# star-tracker-camera-board.net
KiCad netlist of a schematic drawn in EAGLE
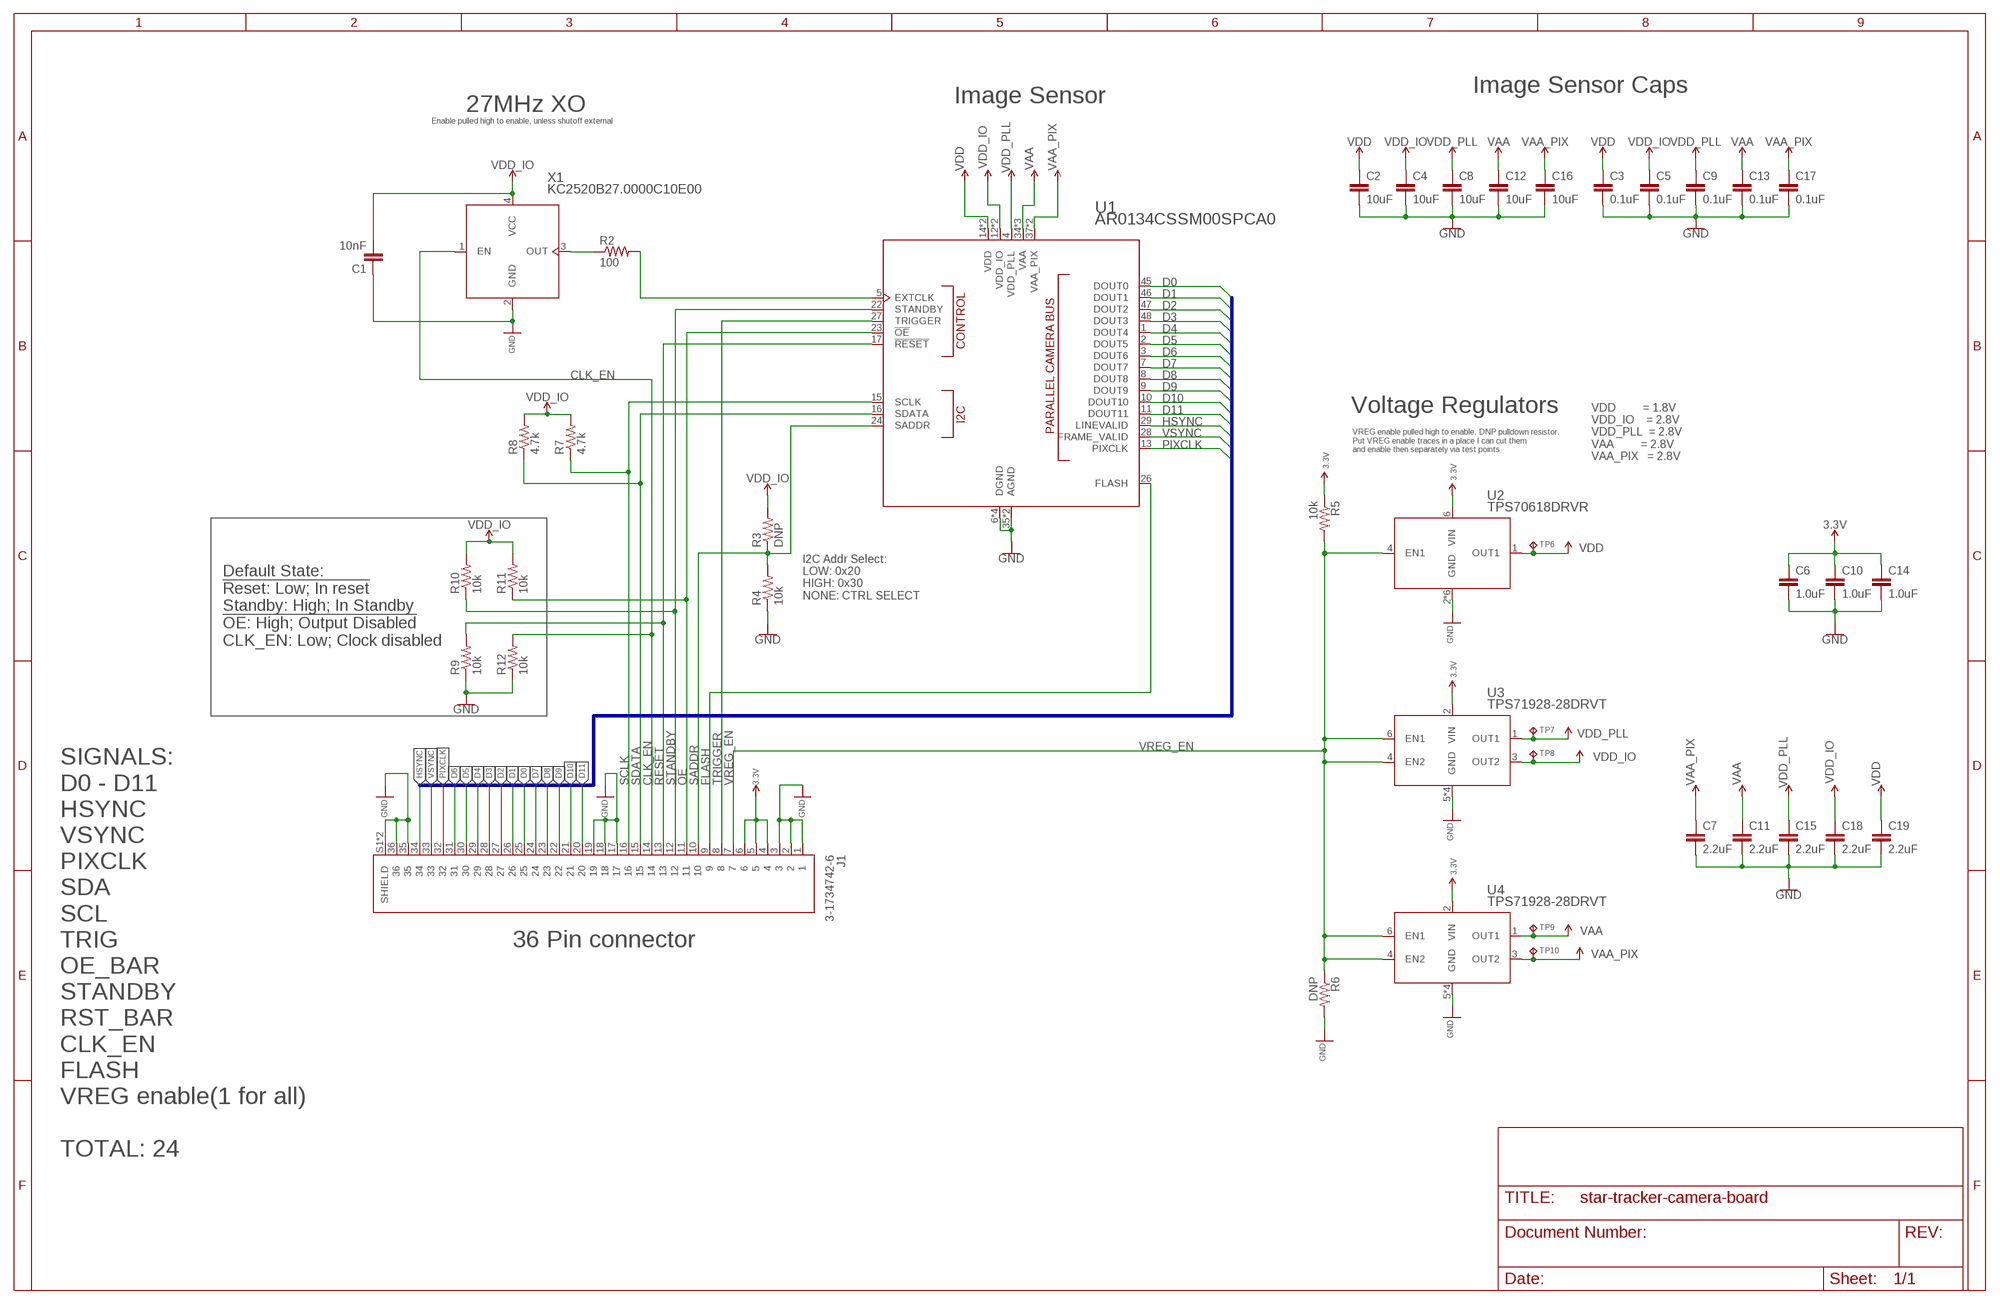
[diagram p0: schematic, sheet 1]

(export (version "E")
  (design (tool "Eeschema 10.0.6"))
  (components
    (comp (ref "C1")
      (value "10nF")
      (footprint "eagle-import:.0402-A-NOSILK")
      (libsource (lib "eagle-import") (part "C-EU0402-A-NOSILK"))
    )
    (comp (ref "C2")
      (value "10uF")
      (footprint "eagle-import:.0603-C-NOSILK")
      (libsource (lib "eagle-import") (part "C-EU0603-C-NOSILK"))
    )
    (comp (ref "C3")
      (value "0.1uF")
      (footprint "eagle-import:.0402-B-NOSILK")
      (libsource (lib "eagle-import") (part "C-EU0402-B-NOSILK"))
    )
    (comp (ref "C4")
      (value "10uF")
      (footprint "eagle-import:.0603-C-NOSILK")
      (libsource (lib "eagle-import") (part "C-EU0603-C-NOSILK"))
    )
    (comp (ref "C5")
      (value "0.1uF")
      (footprint "eagle-import:.0402-B-NOSILK")
      (libsource (lib "eagle-import") (part "C-EU0402-B-NOSILK"))
    )
    (comp (ref "C6")
      (value "1.0uF")
      (footprint "eagle-import:.0603-C-NOSILK")
      (libsource (lib "eagle-import") (part "C-EU0603-C-NOSILK"))
    )
    (comp (ref "C7")
      (value "2.2uF")
      (footprint "eagle-import:.0603-C-NOSILK")
      (libsource (lib "eagle-import") (part "C-EU0603-C-NOSILK"))
    )
    (comp (ref "C8")
      (value "10uF")
      (footprint "eagle-import:.0603-C-NOSILK")
      (libsource (lib "eagle-import") (part "C-EU0603-C-NOSILK"))
    )
    (comp (ref "C9")
      (value "0.1uF")
      (footprint "eagle-import:.0402-B-NOSILK")
      (libsource (lib "eagle-import") (part "C-EU0402-B-NOSILK"))
    )
    (comp (ref "C10")
      (value "1.0uF")
      (footprint "eagle-import:.0603-C-NOSILK")
      (libsource (lib "eagle-import") (part "C-EU0603-C-NOSILK"))
    )
    (comp (ref "C11")
      (value "2.2uF")
      (footprint "eagle-import:.0603-C-NOSILK")
      (libsource (lib "eagle-import") (part "C-EU0603-C-NOSILK"))
    )
    (comp (ref "C12")
      (value "10uF")
      (footprint "eagle-import:.0603-C-NOSILK")
      (libsource (lib "eagle-import") (part "C-EU0603-C-NOSILK"))
    )
    (comp (ref "C13")
      (value "0.1uF")
      (footprint "eagle-import:.0402-B-NOSILK")
      (libsource (lib "eagle-import") (part "C-EU0402-B-NOSILK"))
    )
    (comp (ref "C14")
      (value "1.0uF")
      (footprint "eagle-import:.0603-C-NOSILK")
      (libsource (lib "eagle-import") (part "C-EU0603-C-NOSILK"))
    )
    (comp (ref "C15")
      (value "2.2uF")
      (footprint "eagle-import:.0603-C-NOSILK")
      (libsource (lib "eagle-import") (part "C-EU0603-C-NOSILK"))
    )
    (comp (ref "C16")
      (value "10uF")
      (footprint "eagle-import:.0603-C-NOSILK")
      (libsource (lib "eagle-import") (part "C-EU0603-C-NOSILK"))
    )
    (comp (ref "C17")
      (value "0.1uF")
      (footprint "eagle-import:.0402-B-NOSILK")
      (libsource (lib "eagle-import") (part "C-EU0402-B-NOSILK"))
    )
    (comp (ref "C18")
      (value "2.2uF")
      (footprint "eagle-import:.0603-C-NOSILK")
      (libsource (lib "eagle-import") (part "C-EU0603-C-NOSILK"))
    )
    (comp (ref "C19")
      (value "2.2uF")
      (footprint "eagle-import:.0603-C-NOSILK")
      (libsource (lib "eagle-import") (part "C-EU0603-C-NOSILK"))
    )
    (comp (ref "J1")
      (value "3-1734742-6")
      (footprint "eagle-import:TE_3-1734742-6")
      (libsource (lib "eagle-import") (part "3-1734742-6"))
    )
    (comp (ref "R2")
      (value "100")
      (footprint "eagle-import:.0402-B")
      (libsource (lib "eagle-import") (part "R-US_0402-B"))
    )
    (comp (ref "R3")
      (value "DNP")
      (footprint "eagle-import:.0402-B-NOSILK")
      (libsource (lib "eagle-import") (part "R-US_0402-B-NOSILK"))
    )
    (comp (ref "R4")
      (value "10k")
      (footprint "eagle-import:.0402-B-NOSILK")
      (libsource (lib "eagle-import") (part "R-US_0402-B-NOSILK"))
    )
    (comp (ref "R5")
      (value "10k")
      (footprint "eagle-import:.0402-B-NOSILK")
      (libsource (lib "eagle-import") (part "R-US_0402-B-NOSILK"))
    )
    (comp (ref "R6")
      (value "DNP")
      (footprint "eagle-import:.0402-B-NOSILK")
      (libsource (lib "eagle-import") (part "R-US_0402-B-NOSILK"))
    )
    (comp (ref "R7")
      (value "4.7k")
      (footprint "eagle-import:.0402-B-NOSILK")
      (libsource (lib "eagle-import") (part "R-US_0402-B-NOSILK"))
    )
    (comp (ref "R8")
      (value "4.7k")
      (footprint "eagle-import:.0402-B-NOSILK")
      (libsource (lib "eagle-import") (part "R-US_0402-B-NOSILK"))
    )
    (comp (ref "R9")
      (value "10k")
      (footprint "eagle-import:.0402-B")
      (libsource (lib "eagle-import") (part "R-US_0402-B"))
    )
    (comp (ref "R10")
      (value "10k")
      (footprint "eagle-import:.0402-B")
      (libsource (lib "eagle-import") (part "R-US_0402-B"))
    )
    (comp (ref "R11")
      (value "10k")
      (footprint "eagle-import:.0402-B")
      (libsource (lib "eagle-import") (part "R-US_0402-B"))
    )
    (comp (ref "R12")
      (value "10k")
      (footprint "eagle-import:.0402-B")
      (libsource (lib "eagle-import") (part "R-US_0402-B"))
    )
    (comp (ref "TP6")
      (value "TPTP06R")
      (footprint "eagle-import:TP06R")
      (libsource (lib "eagle-import") (part "TPTP06R"))
    )
    (comp (ref "TP7")
      (value "TPTP06R")
      (footprint "eagle-import:TP06R")
      (libsource (lib "eagle-import") (part "TPTP06R"))
    )
    (comp (ref "TP8")
      (value "TPTP06R")
      (footprint "eagle-import:TP06R")
      (libsource (lib "eagle-import") (part "TPTP06R"))
    )
    (comp (ref "TP9")
      (value "TPTP06R")
      (footprint "eagle-import:TP06R")
      (libsource (lib "eagle-import") (part "TPTP06R"))
    )
    (comp (ref "TP10")
      (value "TPTP06R")
      (footprint "eagle-import:TP06R")
      (libsource (lib "eagle-import") (part "TPTP06R"))
    )
    (comp (ref "U1")
      (value "AR0134CSSM00SPCA0")
      (footprint "eagle-import:AR0134CSSM00SPCA0")
      (libsource (lib "eagle-import") (part "AR0134CSSM00SPCA0"))
    )
    (comp (ref "U2")
      (value "TPS70618DRVR")
      (footprint "eagle-import:DRV6_1P6X1")
      (libsource (lib "eagle-import") (part "TPS70618DRVR"))
    )
    (comp (ref "U3")
      (value "TPS71928-28DRVT")
      (footprint "eagle-import:DRV6_1P6X1")
      (fields (field (name "MPN") "TPS71928-28DRVR"))
      (libsource (lib "eagle-import") (part "TPS71928-28DRVT"))
    )
    (comp (ref "U4")
      (value "TPS71928-28DRVT")
      (footprint "eagle-import:DRV6_1P6X1")
      (fields (field (name "MPN") "TPS71928-28DRVR"))
      (libsource (lib "eagle-import") (part "TPS71928-28DRVT"))
    )
    (comp (ref "X1")
      (value "KC2520B27.0000C10E00")
      (footprint "eagle-import:OSC_KYOCERA_KC2520B")
      (libsource (lib "eagle-import") (part "KC2520B27.0000C10E00"))
    )
  )
  (nets
    (net (code "1") (name "/CLK_EN") (class "Default")
      (node (ref "J1") (pin "14") (pinfunction "14_14") (pintype "passive"))
      (node (ref "R12") (pin "2") (pinfunction "2_2") (pintype "passive"))
      (node (ref "X1") (pin "1") (pinfunction "EN_1") (pintype "passive"))
    )
    (net (code "2") (name "/FLASH") (class "Default")
      (node (ref "J1") (pin "9") (pinfunction "9_9") (pintype "passive"))
      (node (ref "U1") (pin "26") (pinfunction "FLASH_26") (pintype "bidirectional"))
    )
    (net (code "3") (name "/SADDR") (class "Default")
      (node (ref "J1") (pin "10") (pinfunction "10_10") (pintype "passive"))
      (node (ref "R3") (pin "1") (pinfunction "1_1") (pintype "passive"))
      (node (ref "R4") (pin "2") (pinfunction "2_2") (pintype "passive"))
      (node (ref "U1") (pin "24") (pinfunction "SADDR_24") (pintype "bidirectional"))
    )
    (net (code "4") (name "/SCLK") (class "Default")
      (node (ref "J1") (pin "16") (pinfunction "16_16") (pintype "passive"))
      (node (ref "R7") (pin "1") (pinfunction "1_1") (pintype "passive"))
      (node (ref "U1") (pin "15") (pinfunction "SCLK_15") (pintype "bidirectional"))
    )
    (net (code "5") (name "/SDATA") (class "Default")
      (node (ref "J1") (pin "15") (pinfunction "15_15") (pintype "passive"))
      (node (ref "R8") (pin "1") (pinfunction "1_1") (pintype "passive"))
      (node (ref "U1") (pin "16") (pinfunction "SDATA_16") (pintype "bidirectional"))
    )
    (net (code "6") (name "/STANDBY") (class "Default")
      (node (ref "J1") (pin "12") (pinfunction "12_12") (pintype "passive"))
      (node (ref "R10") (pin "1") (pinfunction "1_1") (pintype "passive"))
      (node (ref "U1") (pin "22") (pinfunction "STANDBY_22") (pintype "bidirectional"))
    )
    (net (code "7") (name "/TRIGGER") (class "Default")
      (node (ref "J1") (pin "8") (pinfunction "8_8") (pintype "passive"))
      (node (ref "U1") (pin "27") (pinfunction "TRIGGER_27") (pintype "bidirectional"))
    )
    (net (code "8") (name "/VREG_EN") (class "Default")
      (node (ref "J1") (pin "7") (pinfunction "7_7") (pintype "passive"))
      (node (ref "R5") (pin "2") (pinfunction "2_2") (pintype "passive"))
      (node (ref "R6") (pin "1") (pinfunction "1_1") (pintype "passive"))
      (node (ref "U2") (pin "4") (pinfunction "EN1_4") (pintype "passive"))
      (node (ref "U3") (pin "4") (pinfunction "EN2_4") (pintype "passive"))
      (node (ref "U3") (pin "6") (pinfunction "EN1_6") (pintype "passive"))
      (node (ref "U4") (pin "4") (pinfunction "EN2_4") (pintype "passive"))
      (node (ref "U4") (pin "6") (pinfunction "EN1_6") (pintype "passive"))
    )
    (net (code "9") (name "/~{OE}") (class "Default")
      (node (ref "J1") (pin "11") (pinfunction "11_11") (pintype "passive"))
      (node (ref "R11") (pin "1") (pinfunction "1_1") (pintype "passive"))
      (node (ref "U1") (pin "23") (pinfunction "~{OE}_23") (pintype "bidirectional"))
    )
    (net (code "10") (name "/~{RESET}") (class "Default")
      (node (ref "J1") (pin "13") (pinfunction "13_13") (pintype "passive"))
      (node (ref "R9") (pin "2") (pinfunction "2_2") (pintype "passive"))
      (node (ref "U1") (pin "17") (pinfunction "~{RESET}_17") (pintype "bidirectional"))
    )
    (net (code "11") (name "3.3V") (class "Default")
      (node (ref "C10") (pin "1") (pinfunction "1_1") (pintype "passive"))
      (node (ref "C14") (pin "1") (pinfunction "1_1") (pintype "passive"))
      (node (ref "C6") (pin "1") (pinfunction "1_1") (pintype "passive"))
      (node (ref "J1") (pin "4") (pinfunction "4_4") (pintype "passive"))
      (node (ref "J1") (pin "5") (pinfunction "5_5") (pintype "passive"))
      (node (ref "J1") (pin "6") (pinfunction "6_6") (pintype "passive"))
      (node (ref "R5") (pin "1") (pinfunction "1_1") (pintype "passive"))
      (node (ref "U2") (pin "6") (pinfunction "VIN_6") (pintype "input"))
      (node (ref "U3") (pin "2") (pinfunction "VIN_2") (pintype "power_in"))
      (node (ref "U4") (pin "2") (pinfunction "VIN_2") (pintype "power_in"))
    )
    (net (code "12") (name "D0") (class "Default")
      (node (ref "J1") (pin "25") (pinfunction "25_25") (pintype "passive"))
      (node (ref "U1") (pin "45") (pinfunction "DOUT0_45") (pintype "bidirectional"))
    )
    (net (code "13") (name "D1") (class "Default")
      (node (ref "J1") (pin "26") (pinfunction "26_26") (pintype "passive"))
      (node (ref "U1") (pin "46") (pinfunction "DOUT1_46") (pintype "bidirectional"))
    )
    (net (code "14") (name "D2") (class "Default")
      (node (ref "J1") (pin "27") (pinfunction "27_27") (pintype "passive"))
      (node (ref "U1") (pin "47") (pinfunction "DOUT2_47") (pintype "bidirectional"))
    )
    (net (code "15") (name "D3") (class "Default")
      (node (ref "J1") (pin "28") (pinfunction "28_28") (pintype "passive"))
      (node (ref "U1") (pin "48") (pinfunction "DOUT3_48") (pintype "bidirectional"))
    )
    (net (code "16") (name "D4") (class "Default")
      (node (ref "J1") (pin "29") (pinfunction "29_29") (pintype "passive"))
      (node (ref "U1") (pin "1") (pinfunction "DOUT4_1") (pintype "bidirectional"))
    )
    (net (code "17") (name "D5") (class "Default")
      (node (ref "J1") (pin "30") (pinfunction "30_30") (pintype "passive"))
      (node (ref "U1") (pin "2") (pinfunction "DOUT5_2") (pintype "bidirectional"))
    )
    (net (code "18") (name "D6") (class "Default")
      (node (ref "J1") (pin "31") (pinfunction "31_31") (pintype "passive"))
      (node (ref "U1") (pin "3") (pinfunction "DOUT6_3") (pintype "bidirectional"))
    )
    (net (code "19") (name "D7") (class "Default")
      (node (ref "J1") (pin "24") (pinfunction "24_24") (pintype "passive"))
      (node (ref "U1") (pin "7") (pinfunction "DOUT7_7") (pintype "bidirectional"))
    )
    (net (code "20") (name "D8") (class "Default")
      (node (ref "J1") (pin "23") (pinfunction "23_23") (pintype "passive"))
      (node (ref "U1") (pin "8") (pinfunction "DOUT8_8") (pintype "bidirectional"))
    )
    (net (code "21") (name "D9") (class "Default")
      (node (ref "J1") (pin "22") (pinfunction "22_22") (pintype "passive"))
      (node (ref "U1") (pin "9") (pinfunction "DOUT9_9") (pintype "bidirectional"))
    )
    (net (code "22") (name "D10") (class "Default")
      (node (ref "J1") (pin "21") (pinfunction "21_21") (pintype "passive"))
      (node (ref "U1") (pin "10") (pinfunction "DOUT10_10") (pintype "bidirectional"))
    )
    (net (code "23") (name "D11") (class "Default")
      (node (ref "J1") (pin "20") (pinfunction "20_20") (pintype "passive"))
      (node (ref "U1") (pin "11") (pinfunction "DOUT11_11") (pintype "bidirectional"))
    )
    (net (code "24") (name "GND") (class "Default")
      (node (ref "C1") (pin "1") (pinfunction "1_1") (pintype "passive"))
      (node (ref "C10") (pin "2") (pinfunction "2_2") (pintype "passive"))
      (node (ref "C11") (pin "2") (pinfunction "2_2") (pintype "passive"))
      (node (ref "C12") (pin "2") (pinfunction "2_2") (pintype "passive"))
      (node (ref "C13") (pin "2") (pinfunction "2_2") (pintype "passive"))
      (node (ref "C14") (pin "2") (pinfunction "2_2") (pintype "passive"))
      (node (ref "C15") (pin "2") (pinfunction "2_2") (pintype "passive"))
      (node (ref "C16") (pin "2") (pinfunction "2_2") (pintype "passive"))
      (node (ref "C17") (pin "2") (pinfunction "2_2") (pintype "passive"))
      (node (ref "C18") (pin "2") (pinfunction "2_2") (pintype "passive"))
      (node (ref "C19") (pin "2") (pinfunction "2_2") (pintype "passive"))
      (node (ref "C2") (pin "2") (pinfunction "2_2") (pintype "passive"))
      (node (ref "C3") (pin "2") (pinfunction "2_2") (pintype "passive"))
      (node (ref "C4") (pin "2") (pinfunction "2_2") (pintype "passive"))
      (node (ref "C5") (pin "2") (pinfunction "2_2") (pintype "passive"))
      (node (ref "C6") (pin "2") (pinfunction "2_2") (pintype "passive"))
      (node (ref "C7") (pin "2") (pinfunction "2_2") (pintype "passive"))
      (node (ref "C8") (pin "2") (pinfunction "2_2") (pintype "passive"))
      (node (ref "C9") (pin "2") (pinfunction "2_2") (pintype "passive"))
      (node (ref "J1") (pin "1") (pinfunction "1_1") (pintype "passive"))
      (node (ref "J1") (pin "17") (pinfunction "17_17") (pintype "passive"))
      (node (ref "J1") (pin "18") (pinfunction "18_18") (pintype "passive"))
      (node (ref "J1") (pin "19") (pinfunction "19_19") (pintype "passive"))
      (node (ref "J1") (pin "2") (pinfunction "2_2") (pintype "passive"))
      (node (ref "J1") (pin "3") (pinfunction "3_3") (pintype "passive"))
      (node (ref "J1") (pin "35") (pinfunction "35_35") (pintype "passive"))
      (node (ref "J1") (pin "36") (pinfunction "36_36") (pintype "passive"))
      (node (ref "J1") (pin "S1") (pinfunction "SHIELD_S1") (pintype "passive"))
      (node (ref "J1") (pin "S2") (pinfunction "SHIELD_S2") (pintype "passive"))
      (node (ref "R12") (pin "1") (pinfunction "1_1") (pintype "passive"))
      (node (ref "R4") (pin "1") (pinfunction "1_1") (pintype "passive"))
      (node (ref "R6") (pin "2") (pinfunction "2_2") (pintype "passive"))
      (node (ref "R9") (pin "1") (pinfunction "1_1") (pintype "passive"))
      (node (ref "U1") (pin "25") (pinfunction "DGND_25") (pintype "power_in"))
      (node (ref "U1") (pin "30") (pinfunction "DGND_30") (pintype "power_in"))
      (node (ref "U1") (pin "35") (pinfunction "AGND_35") (pintype "power_in"))
      (node (ref "U1") (pin "39") (pinfunction "AGND_39") (pintype "power_in"))
      (node (ref "U1") (pin "44") (pinfunction "DGND_44") (pintype "power_in"))
      (node (ref "U1") (pin "6") (pinfunction "DGND_6") (pintype "power_in"))
      (node (ref "U2") (pin "2") (pinfunction "GND_2") (pintype "power_in"))
      (node (ref "U2") (pin "3") (pinfunction "GND_3") (pintype "power_in"))
      (node (ref "U2") (pin "5") (pinfunction "GND_5") (pintype "power_in"))
      (node (ref "U2") (pin "7") (pinfunction "GND_7") (pintype "power_in"))
      (node (ref "U2") (pin "8") (pinfunction "GND_8") (pintype "power_in"))
      (node (ref "U2") (pin "9") (pinfunction "GND_9") (pintype "power_in"))
      (node (ref "U3") (pin "5") (pinfunction "GND_5") (pintype "power_in"))
      (node (ref "U3") (pin "7") (pinfunction "GND_7") (pintype "power_in"))
      (node (ref "U3") (pin "8") (pinfunction "GND_8") (pintype "power_in"))
      (node (ref "U3") (pin "9") (pinfunction "GND_9") (pintype "power_in"))
      (node (ref "U4") (pin "5") (pinfunction "GND_5") (pintype "power_in"))
      (node (ref "U4") (pin "7") (pinfunction "GND_7") (pintype "power_in"))
      (node (ref "U4") (pin "8") (pinfunction "GND_8") (pintype "power_in"))
      (node (ref "U4") (pin "9") (pinfunction "GND_9") (pintype "power_in"))
      (node (ref "X1") (pin "2") (pinfunction "GND_2") (pintype "power_in"))
    )
    (net (code "25") (name "HSYNC") (class "Default")
      (node (ref "J1") (pin "34") (pinfunction "34_34") (pintype "passive"))
      (node (ref "U1") (pin "29") (pinfunction "LINEVALID_29") (pintype "bidirectional"))
    )
    (net (code "26") (name "Net-(U1-EXTCLK)") (class "Default")
      (node (ref "R2") (pin "2") (pinfunction "2_2") (pintype "passive"))
      (node (ref "U1") (pin "5") (pinfunction "EXTCLK_5") (pintype "bidirectional"))
    )
    (net (code "27") (name "Net-(X1-OUT)") (class "Default")
      (node (ref "R2") (pin "1") (pinfunction "1_1") (pintype "passive"))
      (node (ref "X1") (pin "3") (pinfunction "OUT_3") (pintype "output"))
    )
    (net (code "28") (name "PIXCLK") (class "Default")
      (node (ref "J1") (pin "32") (pinfunction "32_32") (pintype "passive"))
      (node (ref "U1") (pin "13") (pinfunction "PIXCLK_13") (pintype "bidirectional"))
    )
    (net (code "29") (name "VAA") (class "Default")
      (node (ref "C11") (pin "1") (pinfunction "1_1") (pintype "passive"))
      (node (ref "C12") (pin "1") (pinfunction "1_1") (pintype "passive"))
      (node (ref "C13") (pin "1") (pinfunction "1_1") (pintype "passive"))
      (node (ref "TP9") (pin "TP") (pinfunction "TP_TP") (pintype "input"))
      (node (ref "U1") (pin "34") (pinfunction "VAA_34") (pintype "power_in"))
      (node (ref "U1") (pin "36") (pinfunction "VAA_36") (pintype "power_in"))
      (node (ref "U1") (pin "40") (pinfunction "VAA_40") (pintype "power_in"))
      (node (ref "U4") (pin "1") (pinfunction "OUT1_1") (pintype "power_in"))
    )
    (net (code "30") (name "VAA_PIX") (class "Default")
      (node (ref "C16") (pin "1") (pinfunction "1_1") (pintype "passive"))
      (node (ref "C17") (pin "1") (pinfunction "1_1") (pintype "passive"))
      (node (ref "C7") (pin "1") (pinfunction "1_1") (pintype "passive"))
      (node (ref "TP10") (pin "TP") (pinfunction "TP_TP") (pintype "input"))
      (node (ref "U1") (pin "37") (pinfunction "VAA_PIX_37") (pintype "power_in"))
      (node (ref "U1") (pin "38") (pinfunction "VAA_PIX_38") (pintype "power_in"))
      (node (ref "U4") (pin "3") (pinfunction "OUT2_3") (pintype "power_in"))
    )
    (net (code "31") (name "VDD") (class "Default")
      (node (ref "C19") (pin "1") (pinfunction "1_1") (pintype "passive"))
      (node (ref "C2") (pin "1") (pinfunction "1_1") (pintype "passive"))
      (node (ref "C3") (pin "1") (pinfunction "1_1") (pintype "passive"))
      (node (ref "TP6") (pin "TP") (pinfunction "TP_TP") (pintype "input"))
      (node (ref "U1") (pin "14") (pinfunction "VDD_14") (pintype "power_in"))
      (node (ref "U1") (pin "19") (pinfunction "VDD_19") (pintype "power_in"))
      (node (ref "U2") (pin "1") (pinfunction "OUT1_1") (pintype "passive"))
    )
    (net (code "32") (name "VDD_IO") (class "Default")
      (node (ref "C1") (pin "2") (pinfunction "2_2") (pintype "passive"))
      (node (ref "C18") (pin "1") (pinfunction "1_1") (pintype "passive"))
      (node (ref "C4") (pin "1") (pinfunction "1_1") (pintype "passive"))
      (node (ref "C5") (pin "1") (pinfunction "1_1") (pintype "passive"))
      (node (ref "R10") (pin "2") (pinfunction "2_2") (pintype "passive"))
      (node (ref "R11") (pin "2") (pinfunction "2_2") (pintype "passive"))
      (node (ref "R3") (pin "2") (pinfunction "2_2") (pintype "passive"))
      (node (ref "R7") (pin "2") (pinfunction "2_2") (pintype "passive"))
      (node (ref "R8") (pin "2") (pinfunction "2_2") (pintype "passive"))
      (node (ref "TP8") (pin "TP") (pinfunction "TP_TP") (pintype "input"))
      (node (ref "U1") (pin "12") (pinfunction "VDD_IO_12") (pintype "power_in"))
      (node (ref "U1") (pin "18") (pinfunction "VDD_IO_18") (pintype "power_in"))
      (node (ref "U3") (pin "3") (pinfunction "OUT2_3") (pintype "power_in"))
      (node (ref "X1") (pin "4") (pinfunction "VCC_4") (pintype "power_in"))
    )
    (net (code "33") (name "VDD_PLL") (class "Default")
      (node (ref "C15") (pin "1") (pinfunction "1_1") (pintype "passive"))
      (node (ref "C8") (pin "1") (pinfunction "1_1") (pintype "passive"))
      (node (ref "C9") (pin "1") (pinfunction "1_1") (pintype "passive"))
      (node (ref "TP7") (pin "TP") (pinfunction "TP_TP") (pintype "input"))
      (node (ref "U1") (pin "4") (pinfunction "VDD_PLL_4") (pintype "power_in"))
      (node (ref "U3") (pin "1") (pinfunction "OUT1_1") (pintype "power_in"))
    )
    (net (code "34") (name "VSYNC") (class "Default")
      (node (ref "J1") (pin "33") (pinfunction "33_33") (pintype "passive"))
      (node (ref "U1") (pin "28") (pinfunction "FRAME_VALID_28") (pintype "bidirectional"))
    )
  )
)
